# Sheet1.net
KiCad netlist of a schematic drawn in Altium Designer
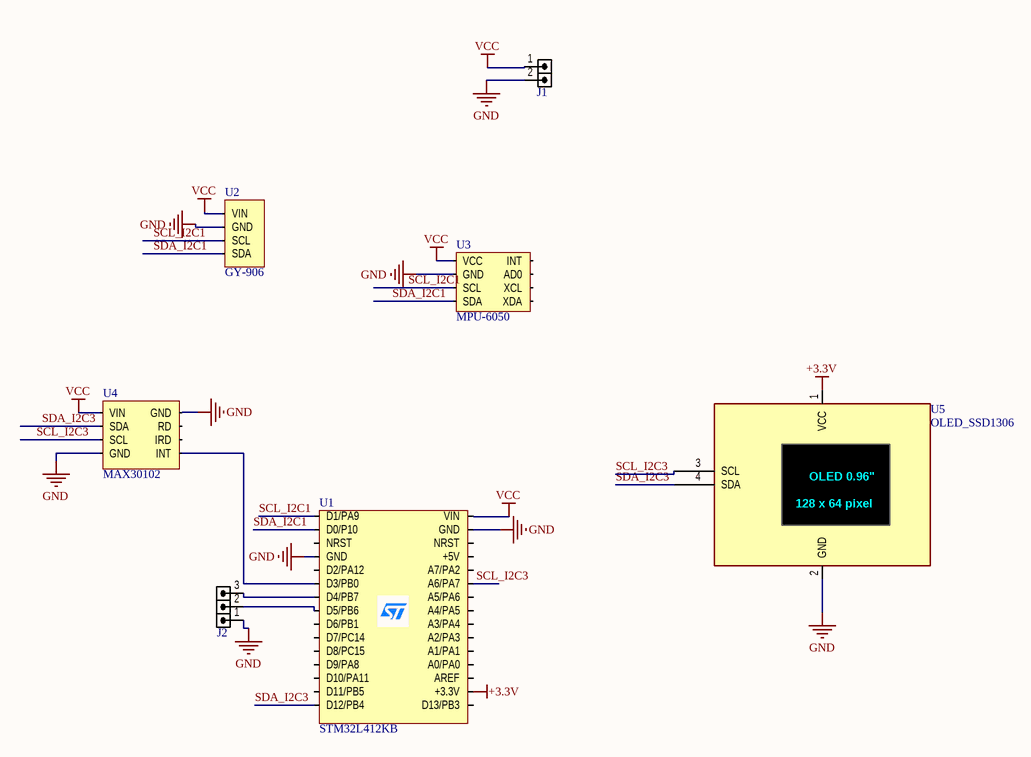
[diagram p0: Sheet1.SchDoc]

(export (version "E")
  (design (tool "Eeschema 10.0.6"))
  (components
    (comp (ref "J1")
      (value "HDRM2")
      (footprint "HDR_M_1X2")
      (description "CONN, HEADER, Male, pitch: 2.54mm, 2POS")
      (libsource (lib "Headers") (part "Header Male THT 1x2"))
    )
    (comp (ref "J2")
      (value "HDRM3")
      (footprint "HDR_M_1X3")
      (description "CONN, HEADER, Male, pitch: 2.54mm, 3POS")
      (libsource (lib "Headers") (part "Header Male THT 1x3"))
    )
    (comp (ref "U1")
      (value "STM32L412KB")
      (footprint "NUCLEO32")
      (libsource (lib "Schlib1") (part "STM32L412KB"))
    )
    (comp (ref "U2") (value "GY-906") (footprint "GY-906") (libsource (lib "Schlib1") (part "GY-906")))
    (comp (ref "U3") (value "MPU-6050") (footprint "MPU-6050") (libsource (lib "Schlib1") (part "MPU-6050")))
    (comp (ref "U4") (value "MAX30102") (footprint "max30102") (libsource (lib "Schlib1") (part "MAX30102")))
    (comp (ref "U5")
      (value "OLED_SSD1306")
      (footprint "OLED_SSD1306_64_I2C")
      (description "MONOCHROME 1.3 128X64")
      (fields
        (field (name "MANUFACTURER") "Adafruit Industries")
        (field (name "MANUFACTURER PART NUMBER") "326")
      )
      (libsource (lib "LCD") (part "OLED_SSD1306_64_I2C"))
    )
  )
  (nets
    (net (code "1") (name "+3.3V") (class "Default")
      (node (ref "U1") (pin "17") (pinfunction "+3.3V_17") (pintype "power_in"))
      (node (ref "U5") (pin "1") (pinfunction "VCC_1") (pintype "passive"))
    )
    (net (code "2") (name "/SCL_I2C1") (class "Default")
      (node (ref "U1") (pin "1") (pinfunction "D1/PA9_1") (pintype "passive"))
      (node (ref "U2") (pin "3") (pinfunction "SCL_3") (pintype "passive"))
      (node (ref "U3") (pin "3") (pinfunction "SCL_3") (pintype "passive"))
    )
    (net (code "3") (name "/SCL_I2C3") (class "Default")
      (node (ref "U1") (pin "25") (pinfunction "A6/PA7_25") (pintype "passive"))
      (node (ref "U4") (pin "3") (pinfunction "SCL_3") (pintype "passive"))
      (node (ref "U5") (pin "3") (pinfunction "SCL_3") (pintype "passive"))
    )
    (net (code "4") (name "/SDA_I2C1") (class "Default")
      (node (ref "U1") (pin "2") (pinfunction "D0/P10_2") (pintype "passive"))
      (node (ref "U2") (pin "4") (pinfunction "SDA_4") (pintype "passive"))
      (node (ref "U3") (pin "4") (pinfunction "SDA_4") (pintype "passive"))
    )
    (net (code "5") (name "/SDA_I2C3") (class "Default")
      (node (ref "U1") (pin "15") (pinfunction "D12/PB4_15") (pintype "passive"))
      (node (ref "U4") (pin "2") (pinfunction "SDA_2") (pintype "passive"))
      (node (ref "U5") (pin "4") (pinfunction "SDA_4") (pintype "passive"))
    )
    (net (code "6") (name "GND") (class "Default")
      (node (ref "J1") (pin "2") (pinfunction "2_2") (pintype "passive"))
      (node (ref "J2") (pin "1") (pinfunction "1_1") (pintype "passive"))
      (node (ref "U1") (pin "29") (pinfunction "GND_29") (pintype "power_in"))
      (node (ref "U1") (pin "4") (pinfunction "GND_4") (pintype "power_in"))
      (node (ref "U2") (pin "2") (pinfunction "GND_2") (pintype "passive"))
      (node (ref "U3") (pin "2") (pinfunction "GND_2") (pintype "passive"))
      (node (ref "U4") (pin "4") (pinfunction "GND_4") (pintype "power_in"))
      (node (ref "U4") (pin "8") (pinfunction "GND_8") (pintype "open_emitter"))
      (node (ref "U5") (pin "2") (pinfunction "GND_2") (pintype "passive"))
    )
    (net (code "7") (name "Net-(U1-D3{slash}PB0)") (class "Default")
      (node (ref "U1") (pin "6") (pinfunction "D3/PB0_6") (pintype "passive"))
      (node (ref "U4") (pin "5") (pinfunction "INT_5") (pintype "passive"))
    )
    (net (code "8") (name "Net-(U1-D4{slash}PB7)") (class "Default")
      (node (ref "J2") (pin "3") (pinfunction "3_3") (pintype "passive"))
      (node (ref "U1") (pin "7") (pinfunction "D4/PB7_7") (pintype "passive"))
    )
    (net (code "9") (name "Net-(U1-D5{slash}PB6)") (class "Default")
      (node (ref "J2") (pin "2") (pinfunction "2_2") (pintype "passive"))
      (node (ref "U1") (pin "8") (pinfunction "D5/PB6_8") (pintype "passive"))
    )
    (net (code "10") (name "VCC") (class "Default")
      (node (ref "J1") (pin "1") (pinfunction "1_1") (pintype "passive"))
      (node (ref "U1") (pin "30") (pinfunction "VIN_30") (pintype "power_in"))
      (node (ref "U2") (pin "1") (pinfunction "VIN_1") (pintype "passive"))
      (node (ref "U3") (pin "1") (pinfunction "VCC_1") (pintype "passive"))
      (node (ref "U4") (pin "1") (pinfunction "VIN_1") (pintype "passive"))
    )
    (net (code "11") (name "unconnected-(U1-+5V-Pad27)") (class "Default")
      (node (ref "U1") (pin "27") (pinfunction "+5V_27") (pintype "power_in"))
    )
    (net (code "12") (name "unconnected-(U1-A0{slash}PA0-Pad19)") (class "Default")
      (node (ref "U1") (pin "19") (pinfunction "A0/PA0_19") (pintype "passive"))
    )
    (net (code "13") (name "unconnected-(U1-A1{slash}PA1-Pad20)") (class "Default")
      (node (ref "U1") (pin "20") (pinfunction "A1/PA1_20") (pintype "passive"))
    )
    (net (code "14") (name "unconnected-(U1-A2{slash}PA3-Pad21)") (class "Default")
      (node (ref "U1") (pin "21") (pinfunction "A2/PA3_21") (pintype "passive"))
    )
    (net (code "15") (name "unconnected-(U1-A3{slash}PA4-Pad22)") (class "Default")
      (node (ref "U1") (pin "22") (pinfunction "A3/PA4_22") (pintype "passive"))
    )
    (net (code "16") (name "unconnected-(U1-A4{slash}PA5-Pad23)") (class "Default")
      (node (ref "U1") (pin "23") (pinfunction "A4/PA5_23") (pintype "passive"))
    )
    (net (code "17") (name "unconnected-(U1-A5{slash}PA6-Pad24)") (class "Default")
      (node (ref "U1") (pin "24") (pinfunction "A5/PA6_24") (pintype "passive"))
    )
    (net (code "18") (name "unconnected-(U1-A7{slash}PA2-Pad26)") (class "Default")
      (node (ref "U1") (pin "26") (pinfunction "A7/PA2_26") (pintype "passive"))
    )
    (net (code "19") (name "unconnected-(U1-AREF-Pad18)") (class "Default")
      (node (ref "U1") (pin "18") (pinfunction "AREF_18") (pintype "power_in"))
    )
    (net (code "20") (name "unconnected-(U1-D2{slash}PA12-Pad5)") (class "Default")
      (node (ref "U1") (pin "5") (pinfunction "D2/PA12_5") (pintype "passive"))
    )
    (net (code "21") (name "unconnected-(U1-D6{slash}PB1-Pad9)") (class "Default")
      (node (ref "U1") (pin "9") (pinfunction "D6/PB1_9") (pintype "passive"))
    )
    (net (code "22") (name "unconnected-(U1-D7{slash}PC14-Pad10)") (class "Default")
      (node (ref "U1") (pin "10") (pinfunction "D7/PC14_10") (pintype "passive"))
    )
    (net (code "23") (name "unconnected-(U1-D8{slash}PC15-Pad11)") (class "Default")
      (node (ref "U1") (pin "11") (pinfunction "D8/PC15_11") (pintype "passive"))
    )
    (net (code "24") (name "unconnected-(U1-D9{slash}PA8-Pad12)") (class "Default")
      (node (ref "U1") (pin "12") (pinfunction "D9/PA8_12") (pintype "passive"))
    )
    (net (code "25") (name "unconnected-(U1-D10{slash}PA11-Pad13)") (class "Default")
      (node (ref "U1") (pin "13") (pinfunction "D10/PA11_13") (pintype "passive"))
    )
    (net (code "26") (name "unconnected-(U1-D11{slash}PB5-Pad14)") (class "Default")
      (node (ref "U1") (pin "14") (pinfunction "D11/PB5_14") (pintype "passive"))
    )
    (net (code "27") (name "unconnected-(U1-D13{slash}PB3-Pad16)") (class "Default")
      (node (ref "U1") (pin "16") (pinfunction "D13/PB3_16") (pintype "passive"))
    )
    (net (code "28") (name "unconnected-(U1-NRST-Pad3)") (class "Default")
      (node (ref "U1") (pin "3") (pinfunction "NRST_3") (pintype "passive"))
    )
    (net (code "29") (name "unconnected-(U1-NRST-Pad28)") (class "Default")
      (node (ref "U1") (pin "28") (pinfunction "NRST_28") (pintype "passive"))
    )
    (net (code "30") (name "unconnected-(U3-AD0-Pad7)") (class "Default")
      (node (ref "U3") (pin "7") (pinfunction "AD0_7") (pintype "passive"))
    )
    (net (code "31") (name "unconnected-(U3-INT-Pad8)") (class "Default")
      (node (ref "U3") (pin "8") (pinfunction "INT_8") (pintype "passive"))
    )
    (net (code "32") (name "unconnected-(U3-XCL-Pad6)") (class "Default")
      (node (ref "U3") (pin "6") (pinfunction "XCL_6") (pintype "passive"))
    )
    (net (code "33") (name "unconnected-(U3-XDA-Pad5)") (class "Default")
      (node (ref "U3") (pin "5") (pinfunction "XDA_5") (pintype "passive"))
    )
    (net (code "34") (name "unconnected-(U4-IRD-Pad6)") (class "Default")
      (node (ref "U4") (pin "6") (pinfunction "IRD_6") (pintype "passive"))
    )
    (net (code "35") (name "unconnected-(U4-RD-Pad7)") (class "Default")
      (node (ref "U4") (pin "7") (pinfunction "RD_7") (pintype "passive"))
    )
  )
)
